# Valve.net
KiCad netlist of a schematic drawn in Altium Designer
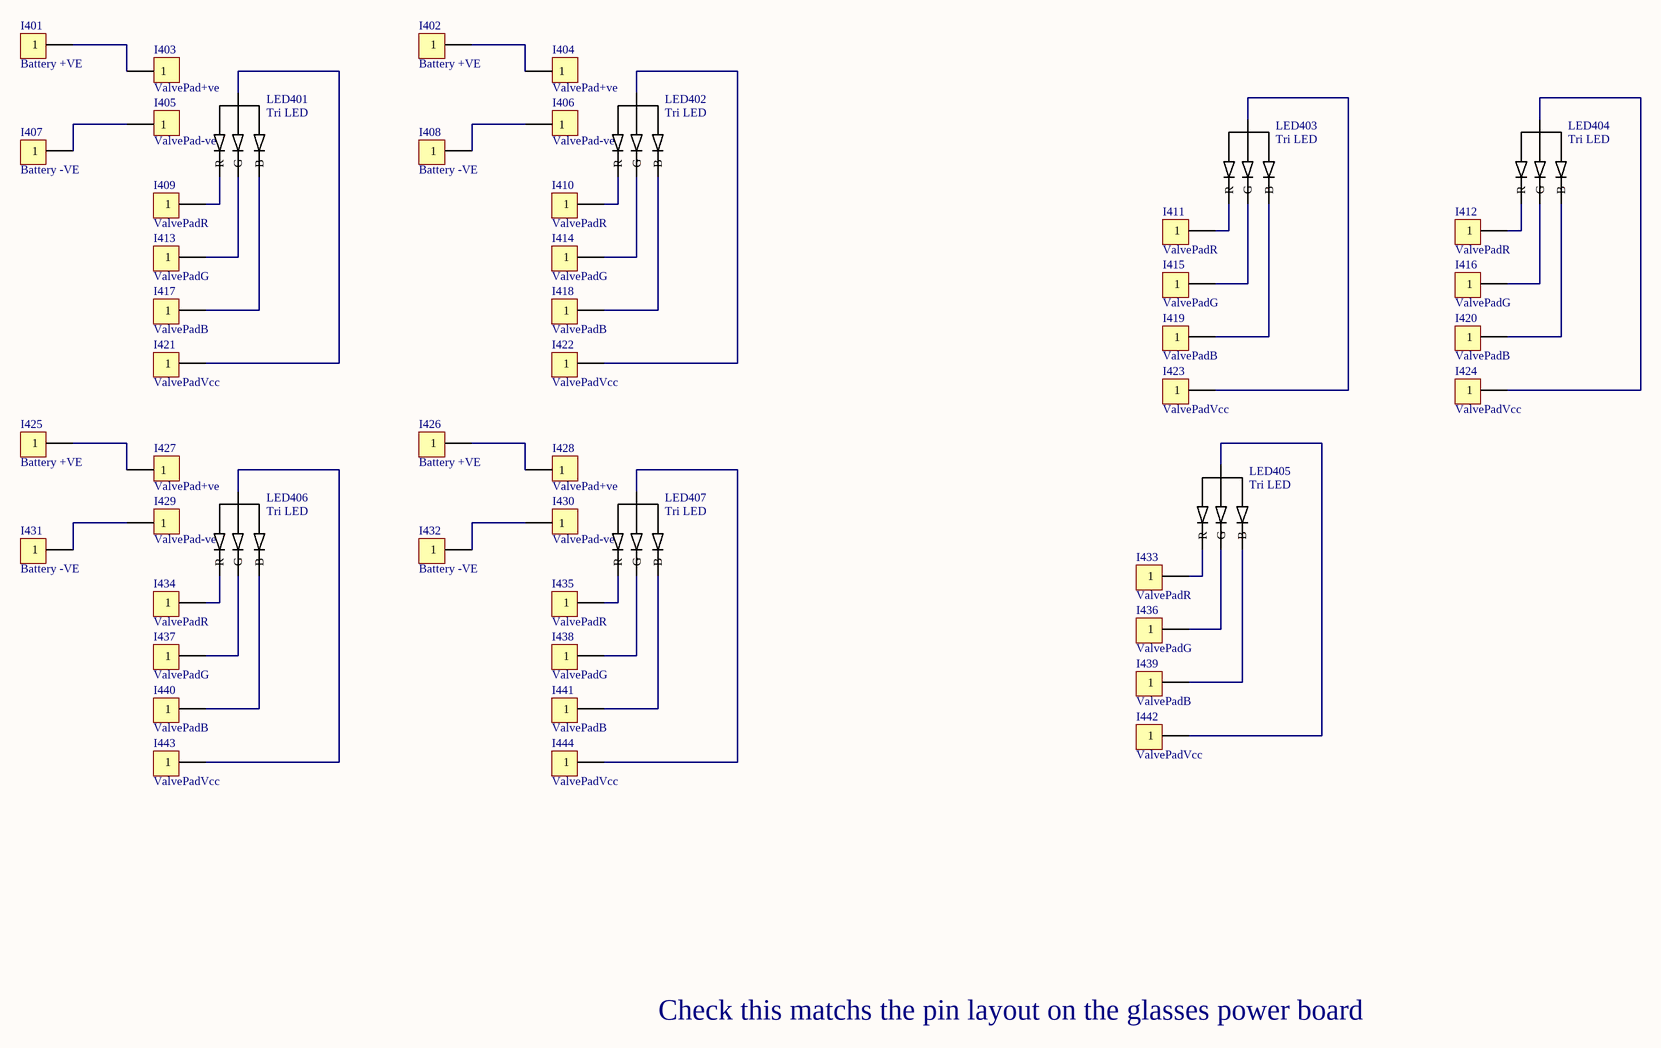
[diagram p0: Valve.SchDoc]

(export (version "E")
  (design (tool "Eeschema 10.0.6"))
  (components
    (comp (ref "I401")
      (value "Battery +VE")
      (footprint "ValveBattery+VE")
      (libsource (lib "Schlib1") (part "TestPoint"))
    )
    (comp (ref "I402")
      (value "Battery +VE")
      (footprint "ValveBattery+VE")
      (libsource (lib "Schlib1") (part "TestPoint"))
    )
    (comp (ref "I403")
      (value "ValvePad+ve")
      (footprint "TestPoint")
      (libsource (lib "") (part "TestPoint_1"))
    )
    (comp (ref "I404")
      (value "ValvePad+ve")
      (footprint "TestPoint")
      (libsource (lib "") (part "TestPoint_1"))
    )
    (comp (ref "I405")
      (value "ValvePad-ve")
      (footprint "TestPoint")
      (libsource (lib "") (part "TestPoint_1"))
    )
    (comp (ref "I406")
      (value "ValvePad-ve")
      (footprint "TestPoint")
      (libsource (lib "") (part "TestPoint_1"))
    )
    (comp (ref "I407")
      (value "Battery -VE")
      (footprint "ValveBattery-VE")
      (libsource (lib "Schlib1") (part "TestPoint"))
    )
    (comp (ref "I408")
      (value "Battery -VE")
      (footprint "ValveBattery-VE")
      (libsource (lib "Schlib1") (part "TestPoint"))
    )
    (comp (ref "I409")
      (value "ValvePadR")
      (footprint "TestPoint")
      (libsource (lib "Schlib1") (part "TestPoint"))
    )
    (comp (ref "I410")
      (value "ValvePadR")
      (footprint "TestPoint")
      (libsource (lib "Schlib1") (part "TestPoint"))
    )
    (comp (ref "I411")
      (value "ValvePadR")
      (footprint "TestPoint")
      (libsource (lib "Schlib1") (part "TestPoint"))
    )
    (comp (ref "I412")
      (value "ValvePadR")
      (footprint "TestPoint")
      (libsource (lib "Schlib1") (part "TestPoint"))
    )
    (comp (ref "I413")
      (value "ValvePadG")
      (footprint "TestPoint")
      (libsource (lib "Schlib1") (part "TestPoint"))
    )
    (comp (ref "I414")
      (value "ValvePadG")
      (footprint "TestPoint")
      (libsource (lib "Schlib1") (part "TestPoint"))
    )
    (comp (ref "I415")
      (value "ValvePadG")
      (footprint "TestPoint")
      (libsource (lib "Schlib1") (part "TestPoint"))
    )
    (comp (ref "I416")
      (value "ValvePadG")
      (footprint "TestPoint")
      (libsource (lib "Schlib1") (part "TestPoint"))
    )
    (comp (ref "I417")
      (value "ValvePadB")
      (footprint "TestPoint")
      (libsource (lib "Schlib1") (part "TestPoint"))
    )
    (comp (ref "I418")
      (value "ValvePadB")
      (footprint "TestPoint")
      (libsource (lib "Schlib1") (part "TestPoint"))
    )
    (comp (ref "I419")
      (value "ValvePadB")
      (footprint "TestPoint")
      (libsource (lib "Schlib1") (part "TestPoint"))
    )
    (comp (ref "I420")
      (value "ValvePadB")
      (footprint "TestPoint")
      (libsource (lib "Schlib1") (part "TestPoint"))
    )
    (comp (ref "I421")
      (value "ValvePadVcc")
      (footprint "TestPoint")
      (libsource (lib "Schlib1") (part "TestPoint"))
    )
    (comp (ref "I422")
      (value "ValvePadVcc")
      (footprint "TestPoint")
      (libsource (lib "Schlib1") (part "TestPoint"))
    )
    (comp (ref "I423")
      (value "ValvePadVcc")
      (footprint "TestPoint")
      (libsource (lib "Schlib1") (part "TestPoint"))
    )
    (comp (ref "I424")
      (value "ValvePadVcc")
      (footprint "TestPoint")
      (libsource (lib "Schlib1") (part "TestPoint"))
    )
    (comp (ref "I425")
      (value "Battery +VE")
      (footprint "ValveBattery+VE")
      (libsource (lib "Schlib1") (part "TestPoint"))
    )
    (comp (ref "I426")
      (value "Battery +VE")
      (footprint "ValveBattery+VE")
      (libsource (lib "Schlib1") (part "TestPoint"))
    )
    (comp (ref "I427")
      (value "ValvePad+ve")
      (footprint "TestPoint")
      (libsource (lib "") (part "TestPoint_1"))
    )
    (comp (ref "I428")
      (value "ValvePad+ve")
      (footprint "TestPoint")
      (libsource (lib "") (part "TestPoint_1"))
    )
    (comp (ref "I429")
      (value "ValvePad-ve")
      (footprint "TestPoint")
      (libsource (lib "") (part "TestPoint_1"))
    )
    (comp (ref "I430")
      (value "ValvePad-ve")
      (footprint "TestPoint")
      (libsource (lib "") (part "TestPoint_1"))
    )
    (comp (ref "I431")
      (value "Battery -VE")
      (footprint "ValveBattery-VE")
      (libsource (lib "Schlib1") (part "TestPoint"))
    )
    (comp (ref "I432")
      (value "Battery -VE")
      (footprint "ValveBattery-VE")
      (libsource (lib "Schlib1") (part "TestPoint"))
    )
    (comp (ref "I433")
      (value "ValvePadR")
      (footprint "TestPoint")
      (libsource (lib "Schlib1") (part "TestPoint"))
    )
    (comp (ref "I434")
      (value "ValvePadR")
      (footprint "TestPoint")
      (libsource (lib "Schlib1") (part "TestPoint"))
    )
    (comp (ref "I435")
      (value "ValvePadR")
      (footprint "TestPoint")
      (libsource (lib "Schlib1") (part "TestPoint"))
    )
    (comp (ref "I436")
      (value "ValvePadG")
      (footprint "TestPoint")
      (libsource (lib "Schlib1") (part "TestPoint"))
    )
    (comp (ref "I437")
      (value "ValvePadG")
      (footprint "TestPoint")
      (libsource (lib "Schlib1") (part "TestPoint"))
    )
    (comp (ref "I438")
      (value "ValvePadG")
      (footprint "TestPoint")
      (libsource (lib "Schlib1") (part "TestPoint"))
    )
    (comp (ref "I439")
      (value "ValvePadB")
      (footprint "TestPoint")
      (libsource (lib "Schlib1") (part "TestPoint"))
    )
    (comp (ref "I440")
      (value "ValvePadB")
      (footprint "TestPoint")
      (libsource (lib "Schlib1") (part "TestPoint"))
    )
    (comp (ref "I441")
      (value "ValvePadB")
      (footprint "TestPoint")
      (libsource (lib "Schlib1") (part "TestPoint"))
    )
    (comp (ref "I442")
      (value "ValvePadVcc")
      (footprint "TestPoint")
      (libsource (lib "Schlib1") (part "TestPoint"))
    )
    (comp (ref "I443")
      (value "ValvePadVcc")
      (footprint "TestPoint")
      (libsource (lib "Schlib1") (part "TestPoint"))
    )
    (comp (ref "I444")
      (value "ValvePadVcc")
      (footprint "TestPoint")
      (libsource (lib "Schlib1") (part "TestPoint"))
    )
    (comp (ref "LED401")
      (value "Tri LED")
      (footprint "CLV1A-FKB")
      (libsource (lib "Schlib1") (part "Tri LED"))
    )
    (comp (ref "LED402")
      (value "Tri LED")
      (footprint "CLV1A-FKB")
      (libsource (lib "Schlib1") (part "Tri LED"))
    )
    (comp (ref "LED403")
      (value "Tri LED")
      (footprint "CLV1A-FKB")
      (libsource (lib "Schlib1") (part "Tri LED"))
    )
    (comp (ref "LED404")
      (value "Tri LED")
      (footprint "CLV1A-FKB")
      (libsource (lib "Schlib1") (part "Tri LED"))
    )
    (comp (ref "LED405")
      (value "Tri LED")
      (footprint "CLV1A-FKB")
      (libsource (lib "Schlib1") (part "Tri LED"))
    )
    (comp (ref "LED406")
      (value "Tri LED")
      (footprint "CLV1A-FKB")
      (libsource (lib "Schlib1") (part "Tri LED"))
    )
    (comp (ref "LED407")
      (value "Tri LED")
      (footprint "CLV1A-FKB")
      (libsource (lib "Schlib1") (part "Tri LED"))
    )
  )
  (nets
    (net (code "1") (name "Net-(I401-Pad1)") (class "Default")
      (node (ref "I401") (pin "1") (pinfunction "1_1") (pintype "passive"))
      (node (ref "I403") (pin "1") (pinfunction "1_1") (pintype "passive"))
    )
    (net (code "2") (name "Net-(I402-Pad1)") (class "Default")
      (node (ref "I402") (pin "1") (pinfunction "1_1") (pintype "passive"))
      (node (ref "I404") (pin "1") (pinfunction "1_1") (pintype "passive"))
    )
    (net (code "3") (name "Net-(I405-Pad1)") (class "Default")
      (node (ref "I405") (pin "1") (pinfunction "1_1") (pintype "passive"))
      (node (ref "I407") (pin "1") (pinfunction "1_1") (pintype "passive"))
    )
    (net (code "4") (name "Net-(I406-Pad1)") (class "Default")
      (node (ref "I406") (pin "1") (pinfunction "1_1") (pintype "passive"))
      (node (ref "I408") (pin "1") (pinfunction "1_1") (pintype "passive"))
    )
    (net (code "5") (name "Net-(I425-Pad1)") (class "Default")
      (node (ref "I425") (pin "1") (pinfunction "1_1") (pintype "passive"))
      (node (ref "I427") (pin "1") (pinfunction "1_1") (pintype "passive"))
    )
    (net (code "6") (name "Net-(I426-Pad1)") (class "Default")
      (node (ref "I426") (pin "1") (pinfunction "1_1") (pintype "passive"))
      (node (ref "I428") (pin "1") (pinfunction "1_1") (pintype "passive"))
    )
    (net (code "7") (name "Net-(I429-Pad1)") (class "Default")
      (node (ref "I429") (pin "1") (pinfunction "1_1") (pintype "passive"))
      (node (ref "I431") (pin "1") (pinfunction "1_1") (pintype "passive"))
    )
    (net (code "8") (name "Net-(I430-Pad1)") (class "Default")
      (node (ref "I430") (pin "1") (pinfunction "1_1") (pintype "passive"))
      (node (ref "I432") (pin "1") (pinfunction "1_1") (pintype "passive"))
    )
    (net (code "9") (name "Net-(LED401-B)") (class "Default")
      (node (ref "I417") (pin "1") (pinfunction "1_1") (pintype "passive"))
      (node (ref "LED401") (pin "3") (pinfunction "B_3") (pintype "passive"))
    )
    (net (code "10") (name "Net-(LED401-Common)") (class "Default")
      (node (ref "I421") (pin "1") (pinfunction "1_1") (pintype "passive"))
      (node (ref "LED401") (pin "2") (pinfunction "Common_2") (pintype "passive"))
    )
    (net (code "11") (name "Net-(LED401-G)") (class "Default")
      (node (ref "I413") (pin "1") (pinfunction "1_1") (pintype "passive"))
      (node (ref "LED401") (pin "4") (pinfunction "G_4") (pintype "passive"))
    )
    (net (code "12") (name "Net-(LED401-R)") (class "Default")
      (node (ref "I409") (pin "1") (pinfunction "1_1") (pintype "passive"))
      (node (ref "LED401") (pin "1") (pinfunction "R_1") (pintype "passive"))
    )
    (net (code "13") (name "Net-(LED402-B)") (class "Default")
      (node (ref "I418") (pin "1") (pinfunction "1_1") (pintype "passive"))
      (node (ref "LED402") (pin "3") (pinfunction "B_3") (pintype "passive"))
    )
    (net (code "14") (name "Net-(LED402-Common)") (class "Default")
      (node (ref "I422") (pin "1") (pinfunction "1_1") (pintype "passive"))
      (node (ref "LED402") (pin "2") (pinfunction "Common_2") (pintype "passive"))
    )
    (net (code "15") (name "Net-(LED402-G)") (class "Default")
      (node (ref "I414") (pin "1") (pinfunction "1_1") (pintype "passive"))
      (node (ref "LED402") (pin "4") (pinfunction "G_4") (pintype "passive"))
    )
    (net (code "16") (name "Net-(LED402-R)") (class "Default")
      (node (ref "I410") (pin "1") (pinfunction "1_1") (pintype "passive"))
      (node (ref "LED402") (pin "1") (pinfunction "R_1") (pintype "passive"))
    )
    (net (code "17") (name "Net-(LED403-B)") (class "Default")
      (node (ref "I419") (pin "1") (pinfunction "1_1") (pintype "passive"))
      (node (ref "LED403") (pin "3") (pinfunction "B_3") (pintype "passive"))
    )
    (net (code "18") (name "Net-(LED403-Common)") (class "Default")
      (node (ref "I423") (pin "1") (pinfunction "1_1") (pintype "passive"))
      (node (ref "LED403") (pin "2") (pinfunction "Common_2") (pintype "passive"))
    )
    (net (code "19") (name "Net-(LED403-G)") (class "Default")
      (node (ref "I415") (pin "1") (pinfunction "1_1") (pintype "passive"))
      (node (ref "LED403") (pin "4") (pinfunction "G_4") (pintype "passive"))
    )
    (net (code "20") (name "Net-(LED403-R)") (class "Default")
      (node (ref "I411") (pin "1") (pinfunction "1_1") (pintype "passive"))
      (node (ref "LED403") (pin "1") (pinfunction "R_1") (pintype "passive"))
    )
    (net (code "21") (name "Net-(LED404-B)") (class "Default")
      (node (ref "I420") (pin "1") (pinfunction "1_1") (pintype "passive"))
      (node (ref "LED404") (pin "3") (pinfunction "B_3") (pintype "passive"))
    )
    (net (code "22") (name "Net-(LED404-Common)") (class "Default")
      (node (ref "I424") (pin "1") (pinfunction "1_1") (pintype "passive"))
      (node (ref "LED404") (pin "2") (pinfunction "Common_2") (pintype "passive"))
    )
    (net (code "23") (name "Net-(LED404-G)") (class "Default")
      (node (ref "I416") (pin "1") (pinfunction "1_1") (pintype "passive"))
      (node (ref "LED404") (pin "4") (pinfunction "G_4") (pintype "passive"))
    )
    (net (code "24") (name "Net-(LED404-R)") (class "Default")
      (node (ref "I412") (pin "1") (pinfunction "1_1") (pintype "passive"))
      (node (ref "LED404") (pin "1") (pinfunction "R_1") (pintype "passive"))
    )
    (net (code "25") (name "Net-(LED405-B)") (class "Default")
      (node (ref "I439") (pin "1") (pinfunction "1_1") (pintype "passive"))
      (node (ref "LED405") (pin "3") (pinfunction "B_3") (pintype "passive"))
    )
    (net (code "26") (name "Net-(LED405-Common)") (class "Default")
      (node (ref "I442") (pin "1") (pinfunction "1_1") (pintype "passive"))
      (node (ref "LED405") (pin "2") (pinfunction "Common_2") (pintype "passive"))
    )
    (net (code "27") (name "Net-(LED405-G)") (class "Default")
      (node (ref "I436") (pin "1") (pinfunction "1_1") (pintype "passive"))
      (node (ref "LED405") (pin "4") (pinfunction "G_4") (pintype "passive"))
    )
    (net (code "28") (name "Net-(LED405-R)") (class "Default")
      (node (ref "I433") (pin "1") (pinfunction "1_1") (pintype "passive"))
      (node (ref "LED405") (pin "1") (pinfunction "R_1") (pintype "passive"))
    )
    (net (code "29") (name "Net-(LED406-B)") (class "Default")
      (node (ref "I440") (pin "1") (pinfunction "1_1") (pintype "passive"))
      (node (ref "LED406") (pin "3") (pinfunction "B_3") (pintype "passive"))
    )
    (net (code "30") (name "Net-(LED406-Common)") (class "Default")
      (node (ref "I443") (pin "1") (pinfunction "1_1") (pintype "passive"))
      (node (ref "LED406") (pin "2") (pinfunction "Common_2") (pintype "passive"))
    )
    (net (code "31") (name "Net-(LED406-G)") (class "Default")
      (node (ref "I437") (pin "1") (pinfunction "1_1") (pintype "passive"))
      (node (ref "LED406") (pin "4") (pinfunction "G_4") (pintype "passive"))
    )
    (net (code "32") (name "Net-(LED406-R)") (class "Default")
      (node (ref "I434") (pin "1") (pinfunction "1_1") (pintype "passive"))
      (node (ref "LED406") (pin "1") (pinfunction "R_1") (pintype "passive"))
    )
    (net (code "33") (name "Net-(LED407-B)") (class "Default")
      (node (ref "I441") (pin "1") (pinfunction "1_1") (pintype "passive"))
      (node (ref "LED407") (pin "3") (pinfunction "B_3") (pintype "passive"))
    )
    (net (code "34") (name "Net-(LED407-Common)") (class "Default")
      (node (ref "I444") (pin "1") (pinfunction "1_1") (pintype "passive"))
      (node (ref "LED407") (pin "2") (pinfunction "Common_2") (pintype "passive"))
    )
    (net (code "35") (name "Net-(LED407-G)") (class "Default")
      (node (ref "I438") (pin "1") (pinfunction "1_1") (pintype "passive"))
      (node (ref "LED407") (pin "4") (pinfunction "G_4") (pintype "passive"))
    )
    (net (code "36") (name "Net-(LED407-R)") (class "Default")
      (node (ref "I435") (pin "1") (pinfunction "1_1") (pintype "passive"))
      (node (ref "LED407") (pin "1") (pinfunction "R_1") (pintype "passive"))
    )
  )
)
